# PowerSection_V2.net
KiCad netlist of a schematic drawn in Altium Designer
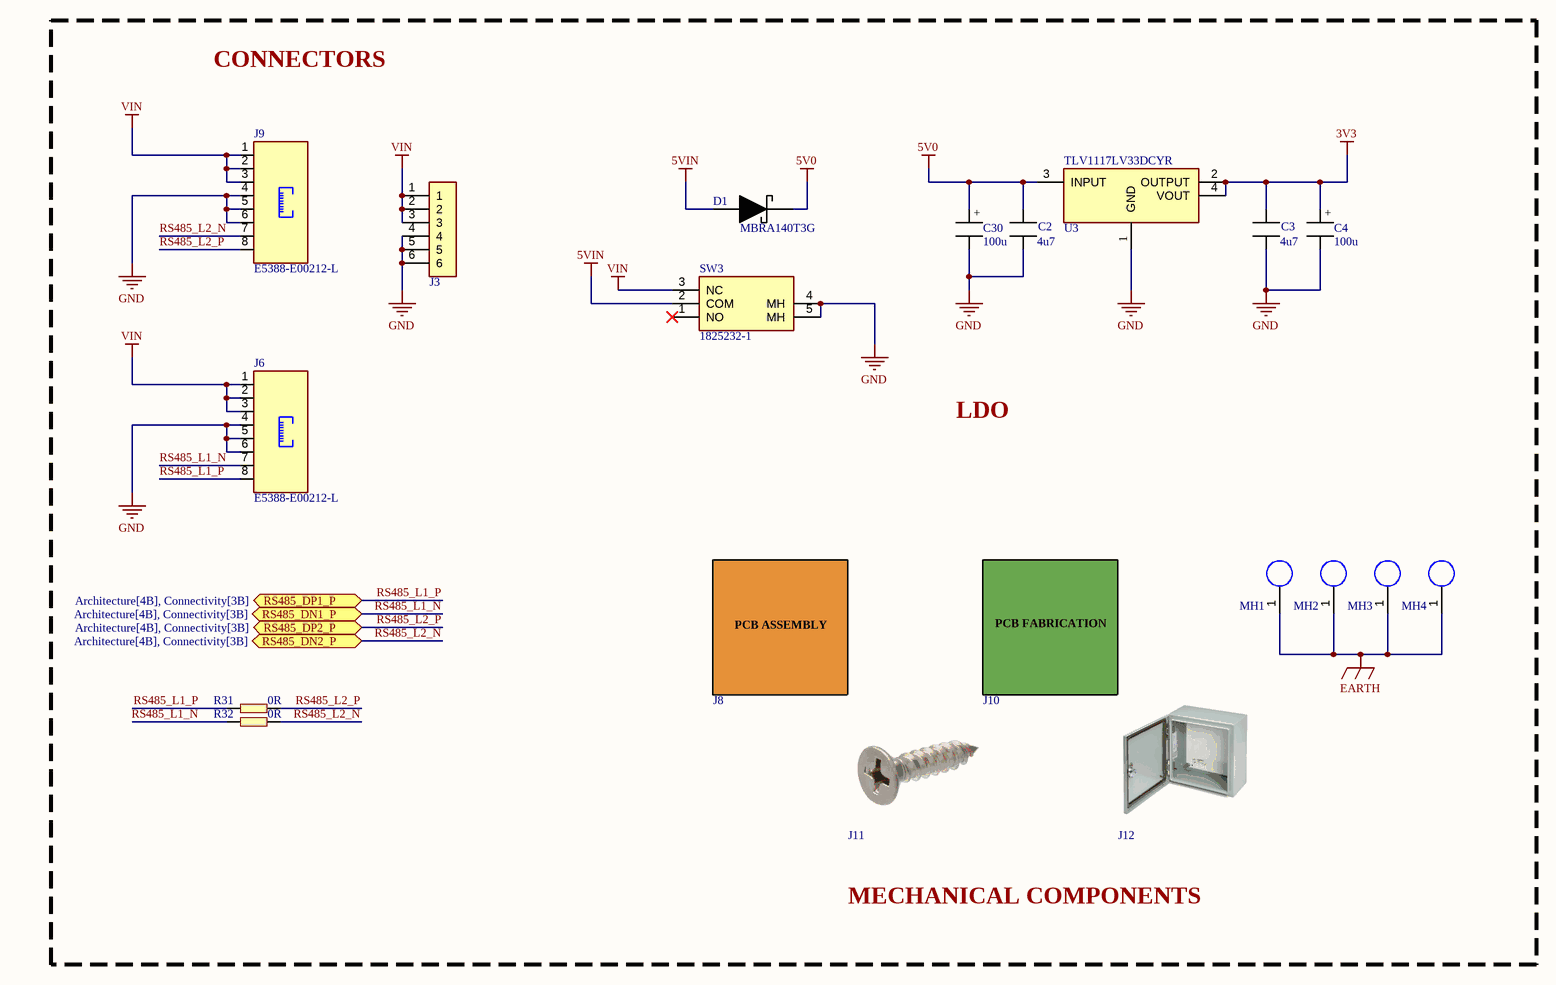
[diagram p0: PowerSection_V2.SchDoc]

(export (version "E")
  (design (tool "Eeschema 10.0.6"))
  (components
    (comp (ref "C2")
      (value "4u7")
      (footprint "CAPC1608X10N")
      (description "MLCC 0603")
      (fields (field (name "Comment") "ERP_102-1"))
      (libsource (lib "Capacitor") (part "MLCC_0603"))
    )
    (comp (ref "C3")
      (value "4u7")
      (footprint "CAPC1608X10N")
      (description "MLCC 0603")
      (fields (field (name "Comment") "ERP_102-1"))
      (libsource (lib "Capacitor") (part "MLCC_0603"))
    )
    (comp (ref "C4")
      (value "100u")
      (footprint "CAP_6.3_7.7")
      (description "Electrolytic Capacitor SMD 6.3x7.7")
      (fields (field (name "Comment") "ERP_102-2"))
      (libsource (lib "ElectrolyticCapacitor") (part "CAP_6.3_7.7"))
    )
    (comp (ref "C30")
      (value "100u")
      (footprint "CAP_6.3_7.7")
      (description "Electrolytic Capacitor SMD 6.3x7.7")
      (fields (field (name "Comment") "ERP_102-2"))
      (libsource (lib "ElectrolyticCapacitor") (part "CAP_6.3_7.7"))
    )
    (comp (ref "D1")
      (value "MBRA140T3G")
      (footprint "SS14_SMA")
      (description "SS14_SMA")
      (fields (field (name "Comment") "ERP_104-3"))
      (libsource (lib "Schottky") (part "SS14_SMA"))
    )
    (comp (ref "J3")
      (value "6Pin_TerminalBlock_5.08P")
      (footprint "6Pin_TerminalBlock_5.08P")
      (description "6PINS TERMINAL BLOCK 5.08 PITCH")
      (libsource (lib "Connectors") (part "6Pin_TerminalBlock_5.08P"))
    )
    (comp (ref "J6")
      (value "E5388-E00212-L")
      (footprint "RJ45")
      (description "CONN MOD JACK 8P8C R/A UNSHLD")
      (fields (field (name "Comment") "ERP_148-3"))
      (libsource (lib "Connectors") (part "RJ45"))
    )
    (comp (ref "J8") (value "APCB") (description "Assembled PCB") (libsource (lib "Jumper") (part "APCB")))
    (comp (ref "J9")
      (value "E5388-E00212-L")
      (footprint "RJ45")
      (description "CONN MOD JACK 8P8C R/A UNSHLD")
      (fields (field (name "Comment") "ERP_148-3"))
      (libsource (lib "Connectors") (part "RJ45"))
    )
    (comp (ref "J10") (value "BPCB") (description "Bare PCB") (libsource (lib "Jumper") (part "BPCB")))
    (comp (ref "J11")
      (value "SCREW")
      (description "Mounting Screw")
      (libsource (lib "Jumper") (part "SCREW"))
    )
    (comp (ref "J12")
      (value "ENCLOSURE")
      (description "PCB Enclosure")
      (libsource (lib "Jumper") (part "ENCLOSURE"))
    )
    (comp (ref "MH1")
      (value "MountingHole4X6")
      (footprint "MountingHole4X6")
      (libsource (lib "Jumper") (part "MountingHole4X6"))
    )
    (comp (ref "MH2")
      (value "MountingHole4X6")
      (footprint "MountingHole4X6")
      (libsource (lib "Jumper") (part "MountingHole4X6"))
    )
    (comp (ref "MH3")
      (value "MountingHole4X6")
      (footprint "MountingHole4X6")
      (libsource (lib "Jumper") (part "MountingHole4X6"))
    )
    (comp (ref "MH4")
      (value "MountingHole4X6")
      (footprint "MountingHole4X6")
      (libsource (lib "Jumper") (part "MountingHole4X6"))
    )
    (comp (ref "R31")
      (value "0R")
      (footprint "RES_0603")
      (description "RES_0603")
      (fields (field (name "Comment") "ERP_101-1"))
      (libsource (lib "Resistor") (part "RES_0603"))
    )
    (comp (ref "R32")
      (value "0R")
      (footprint "RES_0603")
      (description "RES_0603")
      (fields (field (name "Comment") "ERP_101-1"))
      (libsource (lib "Resistor") (part "RES_0603"))
    )
    (comp (ref "SW3")
      (value "1825232-1")
      (footprint "3PIN_SPDT_TH_RA")
      (fields (field (name "Comment") "ERP_110-4"))
      (libsource (lib "Switch") (part "3PIN_SPDT_TH_RA"))
    )
    (comp (ref "U3")
      (value "TLV1117LV33DCYR")
      (footprint "AMS1117_SOT223")
      (description "AMS1117 LDO")
      (fields (field (name "Comment") "ERP_123-1"))
      (libsource (lib "VoltageRegulator") (part "AMS1117_SOT223"))
    )
  )
  (nets
    (net (code "1") (name "/RS485_L1_N") (class "Default")
      (node (ref "J6") (pin "7") (pinfunction "7_7") (pintype "passive"))
      (node (ref "R32") (pin "2") (pinfunction "2_2") (pintype "passive"))
    )
    (net (code "2") (name "/RS485_L1_P") (class "Default")
      (node (ref "J6") (pin "8") (pinfunction "8_8") (pintype "passive"))
      (node (ref "R31") (pin "2") (pinfunction "2_2") (pintype "passive"))
    )
    (net (code "3") (name "/RS485_L2_N") (class "Default")
      (node (ref "J9") (pin "7") (pinfunction "7_7") (pintype "passive"))
      (node (ref "R32") (pin "1") (pinfunction "1_1") (pintype "passive"))
    )
    (net (code "4") (name "/RS485_L2_P") (class "Default")
      (node (ref "J9") (pin "8") (pinfunction "8_8") (pintype "passive"))
      (node (ref "R31") (pin "1") (pinfunction "1_1") (pintype "passive"))
    )
    (net (code "5") (name "3V3") (class "Default")
      (node (ref "C3") (pin "1") (pinfunction "1_1") (pintype "passive"))
      (node (ref "C4") (pin "1") (pinfunction "1_1") (pintype "passive"))
      (node (ref "U3") (pin "2") (pinfunction "OUTPUT_2") (pintype "passive"))
      (node (ref "U3") (pin "4") (pinfunction "VOUT_4") (pintype "passive"))
    )
    (net (code "6") (name "5V0") (class "Default")
      (node (ref "C2") (pin "1") (pinfunction "1_1") (pintype "passive"))
      (node (ref "C30") (pin "1") (pinfunction "1_1") (pintype "passive"))
      (node (ref "D1") (pin "1") (pinfunction "C_1") (pintype "passive"))
      (node (ref "U3") (pin "3") (pinfunction "INPUT_3") (pintype "passive"))
    )
    (net (code "7") (name "5VIN") (class "Default")
      (node (ref "D1") (pin "2") (pinfunction "A_2") (pintype "passive"))
      (node (ref "SW3") (pin "2") (pinfunction "COM_2") (pintype "passive"))
    )
    (net (code "8") (name "EARTH") (class "Default")
      (node (ref "MH1") (pin "1") (pinfunction "1_1") (pintype "passive"))
      (node (ref "MH2") (pin "1") (pinfunction "1_1") (pintype "passive"))
      (node (ref "MH3") (pin "1") (pinfunction "1_1") (pintype "passive"))
      (node (ref "MH4") (pin "1") (pinfunction "1_1") (pintype "passive"))
    )
    (net (code "9") (name "GND") (class "Default")
      (node (ref "C2") (pin "2") (pinfunction "2_2") (pintype "passive"))
      (node (ref "C3") (pin "2") (pinfunction "2_2") (pintype "passive"))
      (node (ref "C30") (pin "2") (pinfunction "2_2") (pintype "passive"))
      (node (ref "C4") (pin "2") (pinfunction "2_2") (pintype "passive"))
      (node (ref "J3") (pin "4") (pinfunction "4_4") (pintype "passive"))
      (node (ref "J3") (pin "5") (pinfunction "5_5") (pintype "passive"))
      (node (ref "J3") (pin "6") (pinfunction "6_6") (pintype "passive"))
      (node (ref "J6") (pin "4") (pinfunction "4_4") (pintype "passive"))
      (node (ref "J6") (pin "5") (pinfunction "5_5") (pintype "passive"))
      (node (ref "J6") (pin "6") (pinfunction "6_6") (pintype "passive"))
      (node (ref "J9") (pin "4") (pinfunction "4_4") (pintype "passive"))
      (node (ref "J9") (pin "5") (pinfunction "5_5") (pintype "passive"))
      (node (ref "J9") (pin "6") (pinfunction "6_6") (pintype "passive"))
      (node (ref "SW3") (pin "4") (pinfunction "MH_4") (pintype "passive"))
      (node (ref "SW3") (pin "5") (pinfunction "MH_5") (pintype "passive"))
      (node (ref "U3") (pin "1") (pinfunction "GND_1") (pintype "power_in"))
    )
    (net (code "10") (name "VIN") (class "Default")
      (node (ref "J3") (pin "1") (pinfunction "1_1") (pintype "passive"))
      (node (ref "J3") (pin "2") (pinfunction "2_2") (pintype "passive"))
      (node (ref "J3") (pin "3") (pinfunction "3_3") (pintype "passive"))
      (node (ref "J6") (pin "1") (pinfunction "1_1") (pintype "passive"))
      (node (ref "J6") (pin "2") (pinfunction "2_2") (pintype "passive"))
      (node (ref "J6") (pin "3") (pinfunction "3_3") (pintype "passive"))
      (node (ref "J9") (pin "1") (pinfunction "1_1") (pintype "passive"))
      (node (ref "J9") (pin "2") (pinfunction "2_2") (pintype "passive"))
      (node (ref "J9") (pin "3") (pinfunction "3_3") (pintype "passive"))
      (node (ref "SW3") (pin "3") (pinfunction "NC_3") (pintype "passive"))
    )
    (net (code "11") (name "unconnected-(SW3-NO-Pad1)") (class "Default")
      (node (ref "SW3") (pin "1") (pinfunction "NO_1") (pintype "passive+no_connect"))
    )
  )
)
